# WEN-_2.net
KiCad netlist of a schematic drawn in EasyEDA Pro
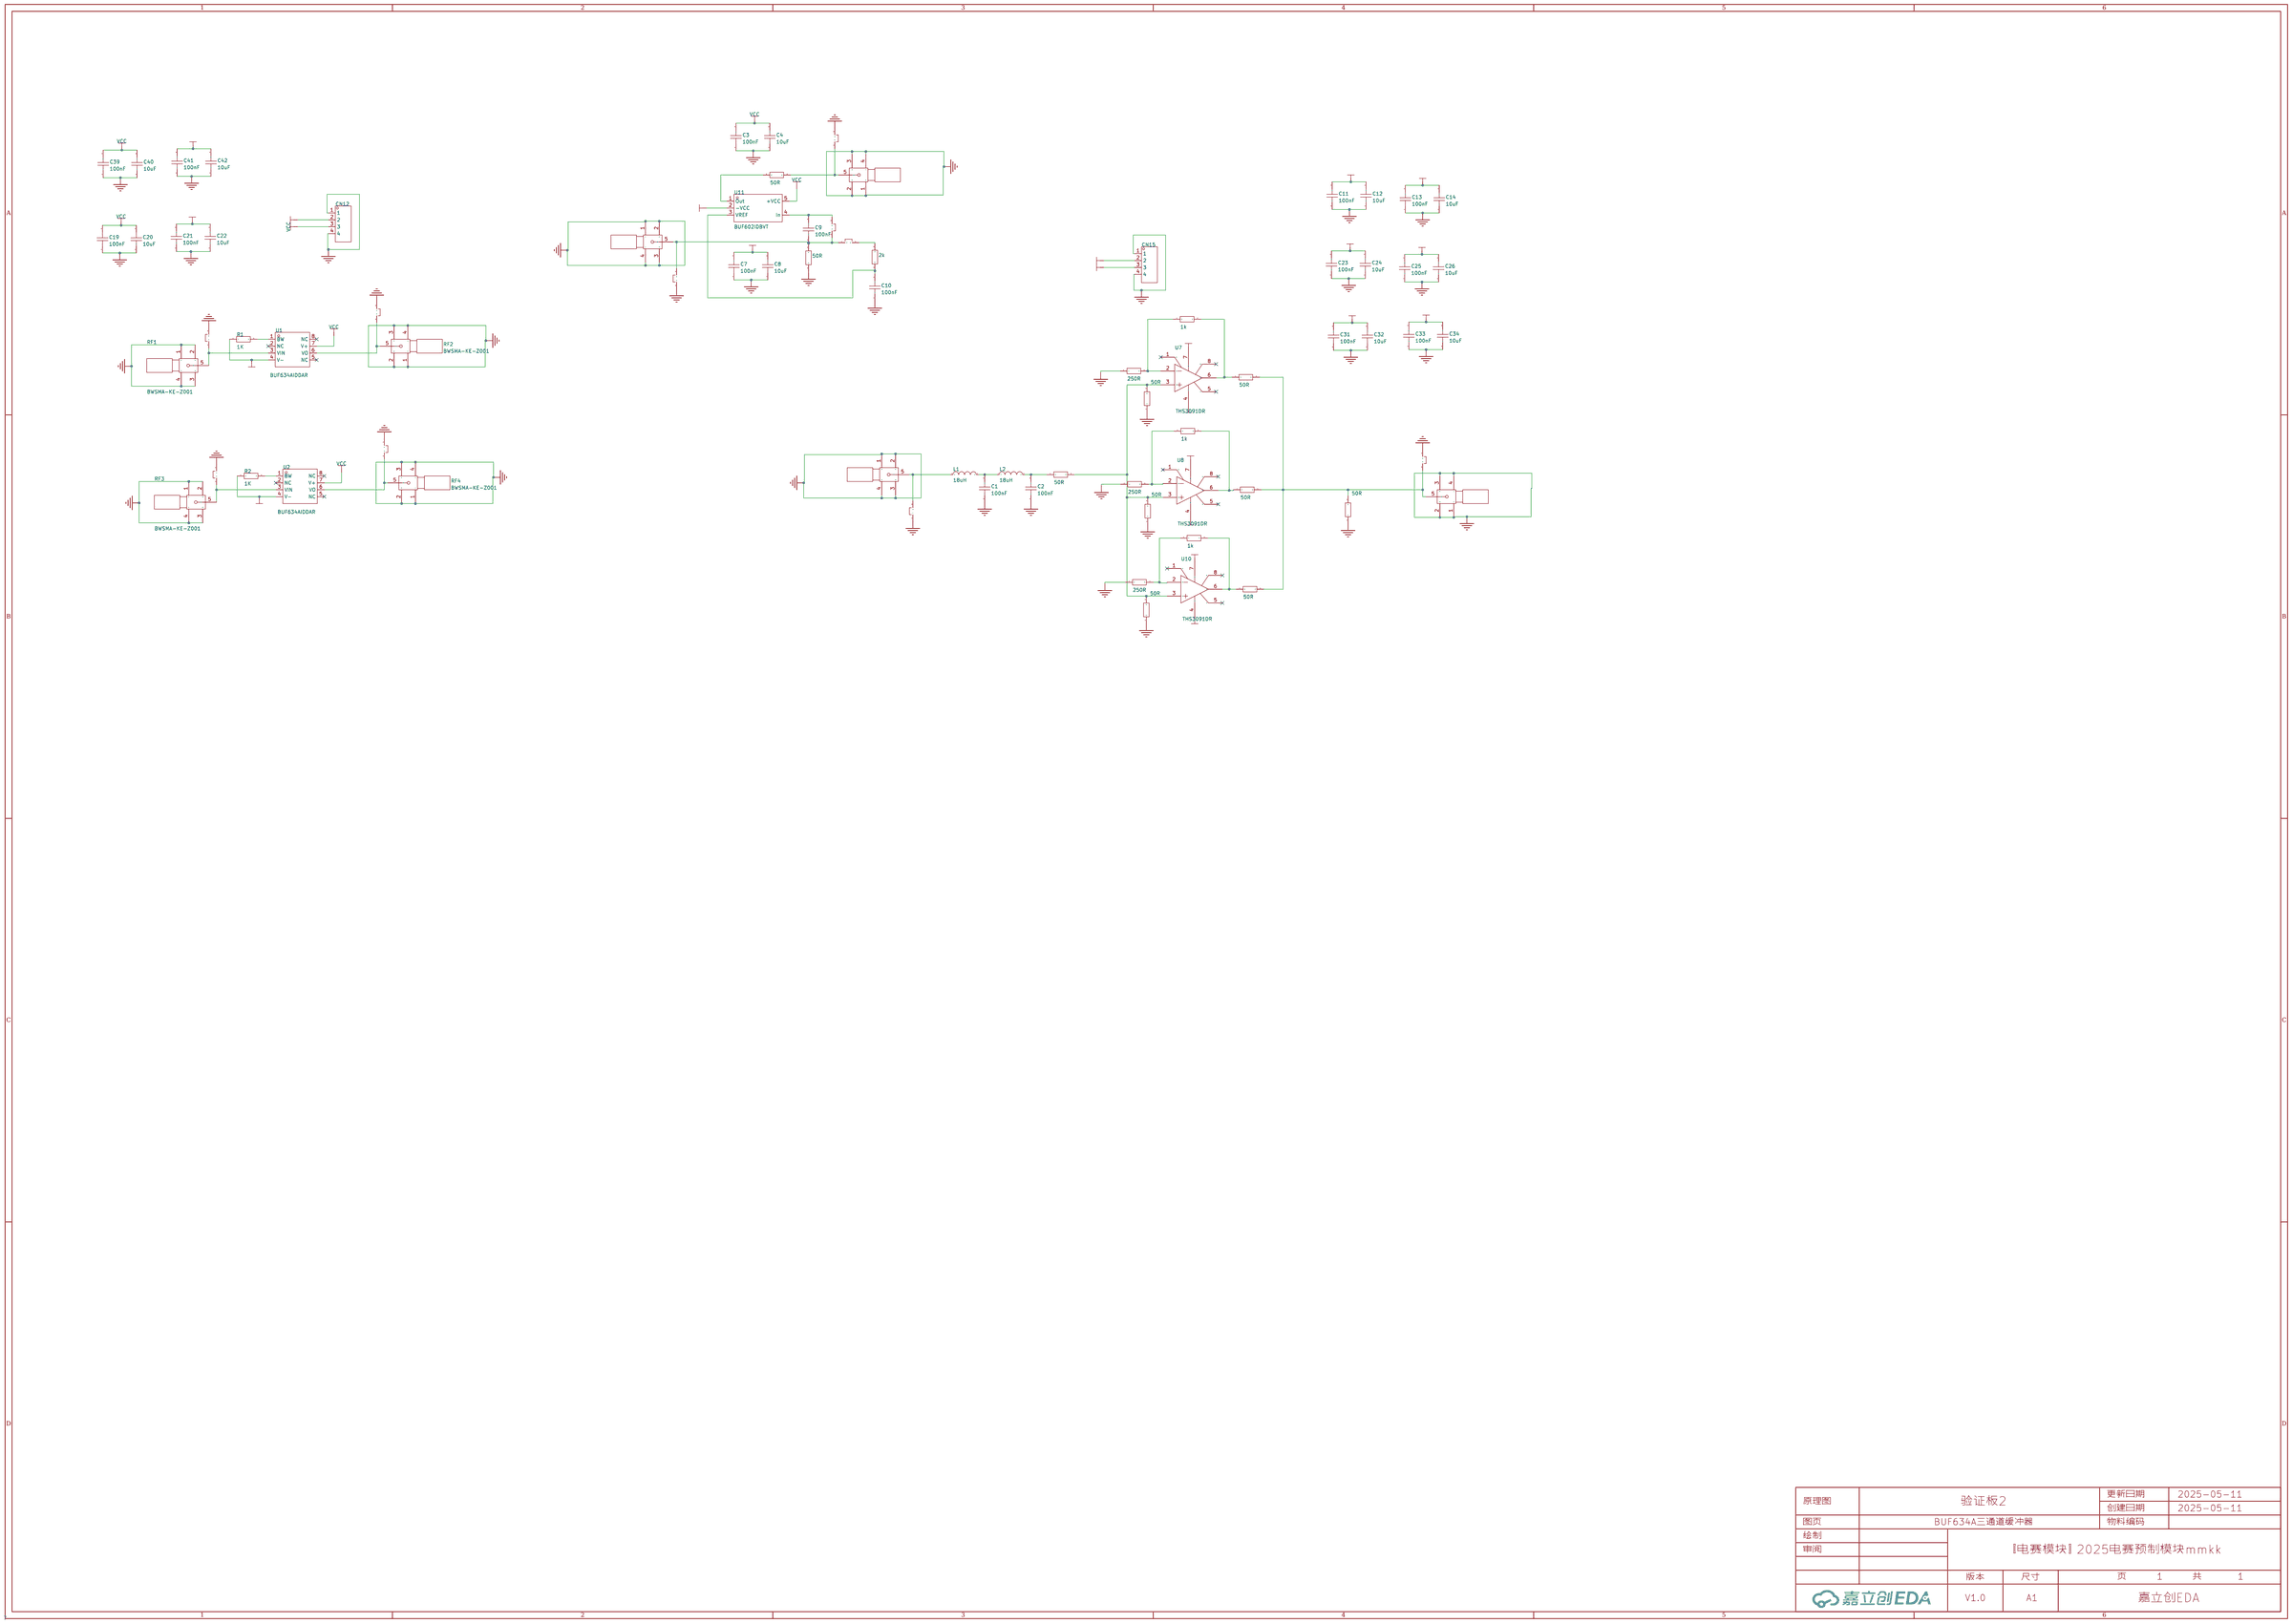
[diagram p0: schematic sheet]

(export (version "E")
  (design (tool "Eeschema 10.0.6"))
  (components
    (comp (ref "C1")
      (value "100nF")
      (footprint "easyedapro:C0805")
      (libsource (lib "easyedapro") (part "CapAcitance"))
    )
    (comp (ref "C2")
      (value "100nF")
      (footprint "easyedapro:C0805")
      (libsource (lib "easyedapro") (part "CapAcitance"))
    )
    (comp (ref "C3")
      (value "100nF")
      (footprint "easyedapro:C0805")
      (libsource (lib "easyedapro") (part "CapAcitance"))
    )
    (comp (ref "C4")
      (value "10uF")
      (footprint "easyedapro:C0805")
      (libsource (lib "easyedapro") (part "CapAcitance"))
    )
    (comp (ref "C7")
      (value "100nF")
      (footprint "easyedapro:C0805")
      (libsource (lib "easyedapro") (part "CapAcitance"))
    )
    (comp (ref "C8")
      (value "10uF")
      (footprint "easyedapro:C0805")
      (libsource (lib "easyedapro") (part "CapAcitance"))
    )
    (comp (ref "C9")
      (value "100nF")
      (footprint "easyedapro:C0805")
      (libsource (lib "easyedapro") (part "CapAcitance"))
    )
    (comp (ref "C10")
      (value "100nF")
      (footprint "easyedapro:C0805")
      (libsource (lib "easyedapro") (part "CapAcitance"))
    )
    (comp (ref "C11")
      (value "100nF")
      (footprint "easyedapro:C0805")
      (libsource (lib "easyedapro") (part "CapAcitance"))
    )
    (comp (ref "C12")
      (value "10uF")
      (footprint "easyedapro:C0805")
      (libsource (lib "easyedapro") (part "CapAcitance"))
    )
    (comp (ref "C13")
      (value "100nF")
      (footprint "easyedapro:C0805")
      (libsource (lib "easyedapro") (part "CapAcitance"))
    )
    (comp (ref "C14")
      (value "10uF")
      (footprint "easyedapro:C0805")
      (libsource (lib "easyedapro") (part "CapAcitance"))
    )
    (comp (ref "C19")
      (value "100nF")
      (footprint "easyedapro:C0805")
      (libsource (lib "easyedapro") (part "CapAcitance"))
    )
    (comp (ref "C20")
      (value "10uF")
      (footprint "easyedapro:C0805")
      (libsource (lib "easyedapro") (part "CapAcitance"))
    )
    (comp (ref "C21")
      (value "100nF")
      (footprint "easyedapro:C0805")
      (libsource (lib "easyedapro") (part "CapAcitance"))
    )
    (comp (ref "C22")
      (value "10uF")
      (footprint "easyedapro:C0805")
      (libsource (lib "easyedapro") (part "CapAcitance"))
    )
    (comp (ref "C23")
      (value "100nF")
      (footprint "easyedapro:C0805")
      (libsource (lib "easyedapro") (part "CapAcitance"))
    )
    (comp (ref "C24")
      (value "10uF")
      (footprint "easyedapro:C0805")
      (libsource (lib "easyedapro") (part "CapAcitance"))
    )
    (comp (ref "C25")
      (value "100nF")
      (footprint "easyedapro:C0805")
      (libsource (lib "easyedapro") (part "CapAcitance"))
    )
    (comp (ref "C26")
      (value "10uF")
      (footprint "easyedapro:C0805")
      (libsource (lib "easyedapro") (part "CapAcitance"))
    )
    (comp (ref "C31")
      (value "100nF")
      (footprint "easyedapro:C0805")
      (libsource (lib "easyedapro") (part "CapAcitance"))
    )
    (comp (ref "C32")
      (value "10uF")
      (footprint "easyedapro:C0805")
      (libsource (lib "easyedapro") (part "CapAcitance"))
    )
    (comp (ref "C33")
      (value "100nF")
      (footprint "easyedapro:C0805")
      (libsource (lib "easyedapro") (part "CapAcitance"))
    )
    (comp (ref "C34")
      (value "10uF")
      (footprint "easyedapro:C0805")
      (libsource (lib "easyedapro") (part "CapAcitance"))
    )
    (comp (ref "C39")
      (value "100nF")
      (footprint "easyedapro:C0805")
      (libsource (lib "easyedapro") (part "CapAcitance"))
    )
    (comp (ref "C40")
      (value "10uF")
      (footprint "easyedapro:C0805")
      (libsource (lib "easyedapro") (part "CapAcitance"))
    )
    (comp (ref "C41")
      (value "100nF")
      (footprint "easyedapro:C0805")
      (libsource (lib "easyedapro") (part "CapAcitance"))
    )
    (comp (ref "C42")
      (value "10uF")
      (footprint "easyedapro:C0805")
      (libsource (lib "easyedapro") (part "CapAcitance"))
    )
    (comp (ref "CN12")
      (value "WJ15EDGVC-3.81-4P")
      (footprint "easyedapro:CONN-TH_4P-P3.81_WJ2EDGVC-3.81-4P")
      (fields (field (name "Manufacturer") "KANGNEX(康奈克斯电气)"))
      (libsource (lib "easyedapro") (part "WJ15EDGVC-3.81-4P"))
    )
    (comp (ref "CN15")
      (value "WJ15EDGVC-3.81-4P")
      (footprint "easyedapro:CONN-TH_4P-P3.81_WJ2EDGVC-3.81-4P")
      (fields (field (name "Manufacturer") "KANGNEX(康奈克斯电气)"))
      (libsource (lib "easyedapro") (part "WJ15EDGVC-3.81-4P"))
    )
    (comp (ref "H1")
      (value "PZ254V-11-02P")
      (footprint "easyedapro:HDR-TH_2P-P2.54-V-M")
      (fields (field (name "Manufacturer") "XFCN(兴飞)"))
      (libsource (lib "easyedapro") (part "PZ254V-11-02P"))
    )
    (comp (ref "H2")
      (value "PZ254V-11-02P")
      (footprint "easyedapro:HDR-TH_2P-P2.54-V-M")
      (fields (field (name "Manufacturer") "XFCN(兴飞)"))
      (libsource (lib "easyedapro") (part "PZ254V-11-02P"))
    )
    (comp (ref "H3")
      (value "PZ254V-11-02P")
      (footprint "easyedapro:HDR-TH_2P-P2.54-V-M")
      (fields (field (name "Manufacturer") "XFCN(兴飞)"))
      (libsource (lib "easyedapro") (part "PZ254V-11-02P"))
    )
    (comp (ref "H4")
      (value "PZ254V-11-02P")
      (footprint "easyedapro:HDR-TH_2P-P2.54-V-M")
      (fields (field (name "Manufacturer") "XFCN(兴飞)"))
      (libsource (lib "easyedapro") (part "PZ254V-11-02P"))
    )
    (comp (ref "H5")
      (value "PZ254V-11-02P")
      (footprint "easyedapro:HDR-TH_2P-P2.54-V-M")
      (fields (field (name "Manufacturer") "XFCN(兴飞)"))
      (libsource (lib "easyedapro") (part "PZ254V-11-02P"))
    )
    (comp (ref "H6")
      (value "PZ254V-11-02P")
      (footprint "easyedapro:HDR-TH_2P-P2.54-V-M")
      (fields (field (name "Manufacturer") "XFCN(兴飞)"))
      (libsource (lib "easyedapro") (part "PZ254V-11-02P"))
    )
    (comp (ref "H7")
      (value "PZ254V-11-02P")
      (footprint "easyedapro:HDR-TH_2P-P2.54-V-M")
      (fields (field (name "Manufacturer") "XFCN(兴飞)"))
      (libsource (lib "easyedapro") (part "PZ254V-11-02P"))
    )
    (comp (ref "H8")
      (value "PZ254V-11-02P")
      (footprint "easyedapro:HDR-TH_2P-P2.54-V-M")
      (fields (field (name "Manufacturer") "XFCN(兴飞)"))
      (libsource (lib "easyedapro") (part "PZ254V-11-02P"))
    )
    (comp (ref "H9")
      (value "PZ254V-11-02P")
      (footprint "easyedapro:HDR-TH_2P-P2.54-V-M")
      (fields (field (name "Manufacturer") "XFCN(兴飞)"))
      (libsource (lib "easyedapro") (part "PZ254V-11-02P"))
    )
    (comp (ref "H10")
      (value "PZ254V-11-02P")
      (footprint "easyedapro:HDR-TH_2P-P2.54-V-M")
      (fields (field (name "Manufacturer") "XFCN(兴飞)"))
      (libsource (lib "easyedapro") (part "PZ254V-11-02P"))
    )
    (comp (ref "L1")
      (value "18uH")
      (footprint "easyedapro:L0805")
      (libsource (lib "easyedapro") (part "SDFL2012S100KTF"))
    )
    (comp (ref "L2")
      (value "18uH")
      (footprint "easyedapro:L0805")
      (libsource (lib "easyedapro") (part "SDFL2012S100KTF"))
    )
    (comp (ref "R1") (value "1K") (footprint "easyedapro:R0603") (libsource (lib "easyedapro") (part "电阻")))
    (comp (ref "R2") (value "1K") (footprint "easyedapro:R0603") (libsource (lib "easyedapro") (part "电阻")))
    (comp (ref "R7") (value "1K") (footprint "easyedapro:R0603") (libsource (lib "easyedapro") (part "电阻")))
    (comp (ref "R8") (value "1K") (footprint "easyedapro:R0603") (libsource (lib "easyedapro") (part "电阻")))
    (comp (ref "R10") (value "1K") (footprint "easyedapro:R0603") (libsource (lib "easyedapro") (part "电阻")))
    (comp (ref "R11") (value "1K") (footprint "easyedapro:R0603") (libsource (lib "easyedapro") (part "电阻")))
    (comp (ref "R12") (value "1K") (footprint "easyedapro:R0603") (libsource (lib "easyedapro") (part "电阻")))
    (comp (ref "R13") (value "1K") (footprint "easyedapro:R0603") (libsource (lib "easyedapro") (part "电阻")))
    (comp (ref "R14") (value "1K") (footprint "easyedapro:R0603") (libsource (lib "easyedapro") (part "电阻")))
    (comp (ref "R15") (value "1K") (footprint "easyedapro:R0603") (libsource (lib "easyedapro") (part "电阻")))
    (comp (ref "R16") (value "1K") (footprint "easyedapro:R0603") (libsource (lib "easyedapro") (part "电阻")))
    (comp (ref "R17") (value "1K") (footprint "easyedapro:R0603") (libsource (lib "easyedapro") (part "电阻")))
    (comp (ref "R18") (value "1K") (footprint "easyedapro:R0603") (libsource (lib "easyedapro") (part "电阻")))
    (comp (ref "R19") (value "1K") (footprint "easyedapro:R0603") (libsource (lib "easyedapro") (part "电阻")))
    (comp (ref "R22") (value "1K") (footprint "easyedapro:R0603") (libsource (lib "easyedapro") (part "电阻")))
    (comp (ref "R23") (value "1K") (footprint "easyedapro:R0603") (libsource (lib "easyedapro") (part "电阻")))
    (comp (ref "R24") (value "1K") (footprint "easyedapro:R0603") (libsource (lib "easyedapro") (part "电阻")))
    (comp (ref "R26") (value "1K") (footprint "easyedapro:R0603") (libsource (lib "easyedapro") (part "电阻")))
    (comp (ref "R27") (value "1K") (footprint "easyedapro:R0603") (libsource (lib "easyedapro") (part "电阻")))
    (comp (ref "RF1")
      (value "BWSMA-KE-Z001")
      (footprint "easyedapro:SMA-TH_BWSMA-KE-Z001")
      (fields (field (name "Manufacturer") "BAT WIRELESS(蝙蝠无线)"))
      (libsource (lib "easyedapro") (part "BWSMA-KE-Z001"))
    )
    (comp (ref "RF2")
      (value "BWSMA-KE-Z001")
      (footprint "easyedapro:SMA-TH_BWSMA-KE-Z001")
      (fields (field (name "Manufacturer") "BAT WIRELESS(蝙蝠无线)"))
      (libsource (lib "easyedapro") (part "BWSMA-KE-Z001"))
    )
    (comp (ref "RF3")
      (value "BWSMA-KE-Z001")
      (footprint "easyedapro:SMA-TH_BWSMA-KE-Z001")
      (fields (field (name "Manufacturer") "BAT WIRELESS(蝙蝠无线)"))
      (libsource (lib "easyedapro") (part "BWSMA-KE-Z001"))
    )
    (comp (ref "RF4")
      (value "BWSMA-KE-Z001")
      (footprint "easyedapro:SMA-TH_BWSMA-KE-Z001")
      (fields (field (name "Manufacturer") "BAT WIRELESS(蝙蝠无线)"))
      (libsource (lib "easyedapro") (part "BWSMA-KE-Z001"))
    )
    (comp (ref "RF5")
      (value "BWSMA-KE-Z001")
      (footprint "easyedapro:SMA-TH_BWSMA-KE-Z001")
      (fields (field (name "Manufacturer") "BAT WIRELESS(蝙蝠无线)"))
      (libsource (lib "easyedapro") (part "BWSMA-KE-Z001"))
    )
    (comp (ref "RF6")
      (value "BWSMA-KE-Z001")
      (footprint "easyedapro:SMA-TH_BWSMA-KE-Z001")
      (fields (field (name "Manufacturer") "BAT WIRELESS(蝙蝠无线)"))
      (libsource (lib "easyedapro") (part "BWSMA-KE-Z001"))
    )
    (comp (ref "RF7")
      (value "BWSMA-KE-Z001")
      (footprint "easyedapro:SMA-TH_BWSMA-KE-Z001")
      (fields (field (name "Manufacturer") "BAT WIRELESS(蝙蝠无线)"))
      (libsource (lib "easyedapro") (part "BWSMA-KE-Z001"))
    )
    (comp (ref "RF8")
      (value "BWSMA-KE-Z001")
      (footprint "easyedapro:SMA-TH_BWSMA-KE-Z001")
      (fields (field (name "Manufacturer") "BAT WIRELESS(蝙蝠无线)"))
      (libsource (lib "easyedapro") (part "BWSMA-KE-Z001"))
    )
    (comp (ref "U1")
      (value "BUF634AIDDAR")
      (footprint "easyedapro:SOIC-8_L4.9-W3.9-P1.27-LS6.0-BL")
      (description "放大器数:单路;轨到轨:-;增益带宽积(GBP):-;输入失调电压(Vos):65mV;压摆率(SR):3750V/us;输入偏置电流(Ib):250nA;")
      (fields (field (name "Manufacturer") "TI(德州仪器)"))
      (libsource (lib "easyedapro") (part "BUF634AIDDAR"))
    )
    (comp (ref "U2")
      (value "BUF634AIDDAR")
      (footprint "easyedapro:SOIC-8_L4.9-W3.9-P1.27-LS6.0-BL")
      (description "放大器数:单路;轨到轨:-;增益带宽积(GBP):-;输入失调电压(Vos):65mV;压摆率(SR):3750V/us;输入偏置电流(Ib):250nA;")
      (fields (field (name "Manufacturer") "TI(德州仪器)"))
      (libsource (lib "easyedapro") (part "BUF634AIDDAR"))
    )
    (comp (ref "U7")
      (value "THS3091DR")
      (footprint "easyedapro:SOIC-8_L4.9-W3.9-P1.27-LS6.0-BL")
      (description "放大器数:单路;增益带宽积(GBP):-;输入偏置电流(Ib):4uA;压摆率(SR):7300V/us;带宽(-3db):235MHz;")
      (fields (field (name "Manufacturer") "TI(德州仪器)"))
      (libsource (lib "easyedapro") (part "THS3091DR"))
    )
    (comp (ref "U8")
      (value "THS3091DR")
      (footprint "easyedapro:SOIC-8_L4.9-W3.9-P1.27-LS6.0-BL")
      (description "放大器数:单路;增益带宽积(GBP):-;输入偏置电流(Ib):4uA;压摆率(SR):7300V/us;带宽(-3db):235MHz;")
      (fields (field (name "Manufacturer") "TI(德州仪器)"))
      (libsource (lib "easyedapro") (part "THS3091DR"))
    )
    (comp (ref "U10")
      (value "THS3091DR")
      (footprint "easyedapro:SOIC-8_L4.9-W3.9-P1.27-LS6.0-BL")
      (description "放大器数:单路;增益带宽积(GBP):-;输入偏置电流(Ib):4uA;压摆率(SR):7300V/us;带宽(-3db):235MHz;")
      (fields (field (name "Manufacturer") "TI(德州仪器)"))
      (libsource (lib "easyedapro") (part "THS3091DR"))
    )
    (comp (ref "U11")
      (value "BUF602IDBVT")
      (footprint "easyedapro:SOT-23-5_L2.9-W1.6-P0.95-LS2.8-BL")
      (description "放大器数:单路;轨到轨:-;增益带宽积(GBP):1GHz;输入失调电压(Vos):30mV;压摆率(SR):8000V/us;输入偏置电流(Ib):3uA;")
      (fields (field (name "Manufacturer") "TI(德州仪器)"))
      (libsource (lib "easyedapro") (part "BUF602IDBVT"))
    )
  )
  (nets
    (net (code "1") (name "GND") (class "Default")
      (node (ref "C1") (pin "1") (pinfunction "1_1") (pintype "input"))
      (node (ref "C10") (pin "1") (pinfunction "1_1") (pintype "input"))
      (node (ref "C11") (pin "1") (pinfunction "1_1") (pintype "input"))
      (node (ref "C12") (pin "1") (pinfunction "1_1") (pintype "input"))
      (node (ref "C13") (pin "1") (pinfunction "1_1") (pintype "input"))
      (node (ref "C14") (pin "1") (pinfunction "1_1") (pintype "input"))
      (node (ref "C19") (pin "1") (pinfunction "1_1") (pintype "input"))
      (node (ref "C2") (pin "1") (pinfunction "1_1") (pintype "input"))
      (node (ref "C20") (pin "1") (pinfunction "1_1") (pintype "input"))
      (node (ref "C21") (pin "1") (pinfunction "1_1") (pintype "input"))
      (node (ref "C22") (pin "1") (pinfunction "1_1") (pintype "input"))
      (node (ref "C23") (pin "1") (pinfunction "1_1") (pintype "input"))
      (node (ref "C24") (pin "1") (pinfunction "1_1") (pintype "input"))
      (node (ref "C25") (pin "1") (pinfunction "1_1") (pintype "input"))
      (node (ref "C26") (pin "1") (pinfunction "1_1") (pintype "input"))
      (node (ref "C3") (pin "1") (pinfunction "1_1") (pintype "input"))
      (node (ref "C31") (pin "1") (pinfunction "1_1") (pintype "input"))
      (node (ref "C32") (pin "1") (pinfunction "1_1") (pintype "input"))
      (node (ref "C33") (pin "1") (pinfunction "1_1") (pintype "input"))
      (node (ref "C34") (pin "1") (pinfunction "1_1") (pintype "input"))
      (node (ref "C39") (pin "1") (pinfunction "1_1") (pintype "input"))
      (node (ref "C4") (pin "1") (pinfunction "1_1") (pintype "input"))
      (node (ref "C40") (pin "1") (pinfunction "1_1") (pintype "input"))
      (node (ref "C41") (pin "1") (pinfunction "1_1") (pintype "input"))
      (node (ref "C42") (pin "1") (pinfunction "1_1") (pintype "input"))
      (node (ref "C7") (pin "1") (pinfunction "1_1") (pintype "input"))
      (node (ref "C8") (pin "1") (pinfunction "1_1") (pintype "input"))
      (node (ref "CN12") (pin "1") (pinfunction "1_1") (pintype "unspecified"))
      (node (ref "CN12") (pin "4") (pinfunction "4_4") (pintype "unspecified"))
      (node (ref "CN15") (pin "1") (pinfunction "1_1") (pintype "unspecified"))
      (node (ref "CN15") (pin "4") (pinfunction "4_4") (pintype "unspecified"))
      (node (ref "H1") (pin "1") (pinfunction "1_1") (pintype "input"))
      (node (ref "H2") (pin "2") (pinfunction "2_2") (pintype "input"))
      (node (ref "H3") (pin "1") (pinfunction "1_1") (pintype "input"))
      (node (ref "H4") (pin "2") (pinfunction "2_2") (pintype "input"))
      (node (ref "H5") (pin "1") (pinfunction "1_1") (pintype "input"))
      (node (ref "H6") (pin "1") (pinfunction "1_1") (pintype "input"))
      (node (ref "H7") (pin "1") (pinfunction "1_1") (pintype "input"))
      (node (ref "H8") (pin "1") (pinfunction "1_1") (pintype "input"))
      (node (ref "R12") (pin "1") (pinfunction "1_1") (pintype "input"))
      (node (ref "R14") (pin "1") (pinfunction "1_1") (pintype "input"))
      (node (ref "R16") (pin "1") (pinfunction "1_1") (pintype "input"))
      (node (ref "R17") (pin "1") (pinfunction "1_1") (pintype "input"))
      (node (ref "R18") (pin "1") (pinfunction "1_1") (pintype "input"))
      (node (ref "R19") (pin "1") (pinfunction "1_1") (pintype "input"))
      (node (ref "R23") (pin "1") (pinfunction "1_1") (pintype "input"))
      (node (ref "R24") (pin "1") (pinfunction "1_1") (pintype "input"))
      (node (ref "RF1") (pin "1") (pinfunction "1_1") (pintype "unspecified"))
      (node (ref "RF1") (pin "2") (pinfunction "2_2") (pintype "unspecified"))
      (node (ref "RF1") (pin "3") (pinfunction "3_3") (pintype "unspecified"))
      (node (ref "RF1") (pin "4") (pinfunction "4_4") (pintype "unspecified"))
      (node (ref "RF2") (pin "1") (pinfunction "1_1") (pintype "unspecified"))
      (node (ref "RF2") (pin "2") (pinfunction "2_2") (pintype "unspecified"))
      (node (ref "RF2") (pin "3") (pinfunction "3_3") (pintype "unspecified"))
      (node (ref "RF2") (pin "4") (pinfunction "4_4") (pintype "unspecified"))
      (node (ref "RF3") (pin "1") (pinfunction "1_1") (pintype "unspecified"))
      (node (ref "RF3") (pin "2") (pinfunction "2_2") (pintype "unspecified"))
      (node (ref "RF3") (pin "3") (pinfunction "3_3") (pintype "unspecified"))
      (node (ref "RF3") (pin "4") (pinfunction "4_4") (pintype "unspecified"))
      (node (ref "RF4") (pin "1") (pinfunction "1_1") (pintype "unspecified"))
      (node (ref "RF4") (pin "2") (pinfunction "2_2") (pintype "unspecified"))
      (node (ref "RF4") (pin "3") (pinfunction "3_3") (pintype "unspecified"))
      (node (ref "RF4") (pin "4") (pinfunction "4_4") (pintype "unspecified"))
      (node (ref "RF5") (pin "1") (pinfunction "1_1") (pintype "unspecified"))
      (node (ref "RF5") (pin "2") (pinfunction "2_2") (pintype "unspecified"))
      (node (ref "RF5") (pin "3") (pinfunction "3_3") (pintype "unspecified"))
      (node (ref "RF5") (pin "4") (pinfunction "4_4") (pintype "unspecified"))
      (node (ref "RF6") (pin "1") (pinfunction "1_1") (pintype "unspecified"))
      (node (ref "RF6") (pin "2") (pinfunction "2_2") (pintype "unspecified"))
      (node (ref "RF6") (pin "3") (pinfunction "3_3") (pintype "unspecified"))
      (node (ref "RF6") (pin "4") (pinfunction "4_4") (pintype "unspecified"))
      (node (ref "RF7") (pin "1") (pinfunction "1_1") (pintype "unspecified"))
      (node (ref "RF7") (pin "2") (pinfunction "2_2") (pintype "unspecified"))
      (node (ref "RF7") (pin "3") (pinfunction "3_3") (pintype "unspecified"))
      (node (ref "RF7") (pin "4") (pinfunction "4_4") (pintype "unspecified"))
      (node (ref "RF8") (pin "1") (pinfunction "1_1") (pintype "unspecified"))
      (node (ref "RF8") (pin "2") (pinfunction "2_2") (pintype "unspecified"))
      (node (ref "RF8") (pin "3") (pinfunction "3_3") (pintype "unspecified"))
      (node (ref "RF8") (pin "4") (pinfunction "4_4") (pintype "unspecified"))
    )
    (net (code "2") (name "Net-(C1-Pad2)") (class "Default")
      (node (ref "C1") (pin "2") (pinfunction "2_2") (pintype "input"))
      (node (ref "L1") (pin "2") (pinfunction "2_2") (pintype "unspecified"))
      (node (ref "L2") (pin "1") (pinfunction "1_1") (pintype "unspecified"))
    )
    (net (code "3") (name "Net-(C2-Pad2)") (class "Default")
      (node (ref "C2") (pin "2") (pinfunction "2_2") (pintype "input"))
      (node (ref "L2") (pin "2") (pinfunction "2_2") (pintype "unspecified"))
      (node (ref "R22") (pin "1") (pinfunction "1_1") (pintype "input"))
    )
    (net (code "4") (name "Net-(C9-Pad1)") (class "Default")
      (node (ref "C9") (pin "1") (pinfunction "1_1") (pintype "input"))
      (node (ref "H10") (pin "1") (pinfunction "1_1") (pintype "input"))
      (node (ref "H7") (pin "2") (pinfunction "2_2") (pintype "input"))
      (node (ref "H9") (pin "2") (pinfunction "2_2") (pintype "input"))
      (node (ref "R24") (pin "2") (pinfunction "2_2") (pintype "input"))
      (node (ref "RF7") (pin "5") (pinfunction "5_5") (pintype "unspecified"))
    )
    (net (code "5") (name "Net-(H5-Pad2)") (class "Default")
      (node (ref "H5") (pin "2") (pinfunction "2_2") (pintype "input"))
      (node (ref "L1") (pin "1") (pinfunction "1_1") (pintype "unspecified"))
      (node (ref "RF5") (pin "5") (pinfunction "5_5") (pintype "unspecified"))
    )
    (net (code "6") (name "Net-(H6-Pad2)") (class "Default")
      (node (ref "H6") (pin "2") (pinfunction "2_2") (pintype "input"))
      (node (ref "R10") (pin "2") (pinfunction "2_2") (pintype "input"))
      (node (ref "R23") (pin "2") (pinfunction "2_2") (pintype "input"))
      (node (ref "R7") (pin "2") (pinfunction "2_2") (pintype "input"))
      (node (ref "R8") (pin "2") (pinfunction "2_2") (pintype "input"))
      (node (ref "RF6") (pin "5") (pinfunction "5_5") (pintype "unspecified"))
    )
    (net (code "7") (name "Net-(H8-Pad2)") (class "Default")
      (node (ref "H8") (pin "2") (pinfunction "2_2") (pintype "input"))
      (node (ref "R26") (pin "1") (pinfunction "1_1") (pintype "input"))
      (node (ref "RF8") (pin "5") (pinfunction "5_5") (pintype "unspecified"))
    )
    (net (code "8") (name "Net-(H10-Pad2)") (class "Default")
      (node (ref "H10") (pin "2") (pinfunction "2_2") (pintype "input"))
      (node (ref "R27") (pin "2") (pinfunction "2_2") (pintype "input"))
    )
    (net (code "9") (name "Net-(U1-BW)") (class "Default")
      (node (ref "R1") (pin "2") (pinfunction "2_2") (pintype "input"))
      (node (ref "U1") (pin "1") (pinfunction "BW_1") (pintype "unspecified"))
    )
    (net (code "10") (name "Net-(U1-VIN)") (class "Default")
      (node (ref "H2") (pin "1") (pinfunction "1_1") (pintype "input"))
      (node (ref "RF1") (pin "5") (pinfunction "5_5") (pintype "unspecified"))
      (node (ref "U1") (pin "3") (pinfunction "VIN_3") (pintype "unspecified"))
    )
    (net (code "11") (name "Net-(U1-VO)") (class "Default")
      (node (ref "H1") (pin "2") (pinfunction "2_2") (pintype "input"))
      (node (ref "RF2") (pin "5") (pinfunction "5_5") (pintype "unspecified"))
      (node (ref "U1") (pin "6") (pinfunction "VO_6") (pintype "unspecified"))
    )
    (net (code "12") (name "Net-(U2-BW)") (class "Default")
      (node (ref "R2") (pin "2") (pinfunction "2_2") (pintype "input"))
      (node (ref "U2") (pin "1") (pinfunction "BW_1") (pintype "unspecified"))
    )
    (net (code "13") (name "Net-(U2-VIN)") (class "Default")
      (node (ref "H4") (pin "1") (pinfunction "1_1") (pintype "input"))
      (node (ref "RF3") (pin "5") (pinfunction "5_5") (pintype "unspecified"))
      (node (ref "U2") (pin "3") (pinfunction "VIN_3") (pintype "unspecified"))
    )
    (net (code "14") (name "Net-(U2-VO)") (class "Default")
      (node (ref "H3") (pin "2") (pinfunction "2_2") (pintype "input"))
      (node (ref "RF4") (pin "5") (pinfunction "5_5") (pintype "unspecified"))
      (node (ref "U2") (pin "6") (pinfunction "VO_6") (pintype "unspecified"))
    )
    (net (code "15") (name "Net-(U7-VIN-)") (class "Default")
      (node (ref "R11") (pin "1") (pinfunction "1_1") (pintype "input"))
      (node (ref "R12") (pin "2") (pinfunction "2_2") (pintype "input"))
      (node (ref "U7") (pin "2") (pinfunction "VIN-_2") (pintype "unspecified"))
    )
    (net (code "16") (name "Net-(U7-VOUT)") (class "Default")
      (node (ref "R11") (pin "2") (pinfunction "2_2") (pintype "input"))
      (node (ref "R7") (pin "1") (pinfunction "1_1") (pintype "input"))
      (node (ref "U7") (pin "6") (pinfunction "VOUT_6") (pintype "output"))
    )
    (net (code "17") (name "Net-(U8-VIN-)") (class "Default")
      (node (ref "R13") (pin "1") (pinfunction "1_1") (pintype "input"))
      (node (ref "R14") (pin "2") (pinfunction "2_2") (pintype "input"))
      (node (ref "U8") (pin "2") (pinfunction "VIN-_2") (pintype "unspecified"))
    )
    (net (code "18") (name "Net-(U8-VOUT)") (class "Default")
      (node (ref "R13") (pin "2") (pinfunction "2_2") (pintype "input"))
      (node (ref "R8") (pin "1") (pinfunction "1_1") (pintype "input"))
      (node (ref "U8") (pin "6") (pinfunction "VOUT_6") (pintype "output"))
    )
    (net (code "19") (name "Net-(U10-VIN+)") (class "Default")
      (node (ref "R17") (pin "2") (pinfunction "2_2") (pintype "input"))
      (node (ref "R18") (pin "2") (pinfunction "2_2") (pintype "input"))
      (node (ref "R19") (pin "2") (pinfunction "2_2") (pintype "input"))
      (node (ref "R22") (pin "2") (pinfunction "2_2") (pintype "input"))
      (node (ref "U10") (pin "3") (pinfunction "VIN+_3") (pintype "unspecified"))
      (node (ref "U7") (pin "3") (pinfunction "VIN+_3") (pintype "unspecified"))
      (node (ref "U8") (pin "3") (pinfunction "VIN+_3") (pintype "unspecified"))
    )
    (net (code "20") (name "Net-(U10-VIN-)") (class "Default")
      (node (ref "R15") (pin "1") (pinfunction "1_1") (pintype "input"))
      (node (ref "R16") (pin "2") (pinfunction "2_2") (pintype "input"))
      (node (ref "U10") (pin "2") (pinfunction "VIN-_2") (pintype "unspecified"))
    )
    (net (code "21") (name "Net-(U10-VOUT)") (class "Default")
      (node (ref "R10") (pin "1") (pinfunction "1_1") (pintype "input"))
      (node (ref "R15") (pin "2") (pinfunction "2_2") (pintype "input"))
      (node (ref "U10") (pin "6") (pinfunction "VOUT_6") (pintype "output"))
    )
    (net (code "22") (name "Net-(U11-In)") (class "Default")
      (node (ref "C9") (pin "2") (pinfunction "2_2") (pintype "input"))
      (node (ref "H9") (pin "1") (pinfunction "1_1") (pintype "input"))
      (node (ref "U11") (pin "4") (pinfunction "In_4") (pintype "unspecified"))
    )
    (net (code "23") (name "Net-(U11-Out)") (class "Default")
      (node (ref "R26") (pin "2") (pinfunction "2_2") (pintype "input"))
      (node (ref "U11") (pin "1") (pinfunction "Out_1") (pintype "unspecified"))
    )
    (net (code "24") (name "Net-(U11-VREF)") (class "Default")
      (node (ref "C10") (pin "2") (pinfunction "2_2") (pintype "input"))
      (node (ref "R27") (pin "1") (pinfunction "1_1") (pintype "input"))
      (node (ref "U11") (pin "3") (pinfunction "VREF_3") (pintype "unspecified"))
    )
    (net (code "25") (name "VCC") (class "Default")
      (node (ref "C19") (pin "2") (pinfunction "2_2") (pintype "input"))
      (node (ref "C20") (pin "2") (pinfunction "2_2") (pintype "input"))
      (node (ref "C3") (pin "2") (pinfunction "2_2") (pintype "input"))
      (node (ref "C39") (pin "2") (pinfunction "2_2") (pintype "input"))
      (node (ref "C4") (pin "2") (pinfunction "2_2") (pintype "input"))
      (node (ref "C40") (pin "2") (pinfunction "2_2") (pintype "input"))
      (node (ref "CN12") (pin "3") (pinfunction "3_3") (pintype "unspecified"))
      (node (ref "U1") (pin "7") (pinfunction "V+_7") (pintype "unspecified"))
      (node (ref "U11") (pin "5") (pinfunction "+VCC_5") (pintype "unspecified"))
      (node (ref "U2") (pin "7") (pinfunction "V+_7") (pintype "unspecified"))
    )
    (net (code "26") (name "VDD") (class "Default")
      (node (ref "C11") (pin "2") (pinfunction "2_2") (pintype "input"))
      (node (ref "C12") (pin "2") (pinfunction "2_2") (pintype "input"))
      (node (ref "C23") (pin "2") (pinfunction "2_2") (pintype "input"))
      (node (ref "C24") (pin "2") (pinfunction "2_2") (pintype "input"))
      (node (ref "C31") (pin "2") (pinfunction "2_2") (pintype "input"))
      (node (ref "C32") (pin "2") (pinfunction "2_2") (pintype "input"))
      (node (ref "CN15") (pin "2") (pinfunction "2_2") (pintype "unspecified"))
      (node (ref "U10") (pin "7") (pinfunction "VS+_7") (pintype "unspecified"))
      (node (ref "U7") (pin "7") (pinfunction "VS+_7") (pintype "unspecified"))
      (node (ref "U8") (pin "7") (pinfunction "VS+_7") (pintype "unspecified"))
    )
    (net (code "27") (name "VEE") (class "Default")
      (node (ref "C21") (pin "2") (pinfunction "2_2") (pintype "input"))
      (node (ref "C22") (pin "2") (pinfunction "2_2") (pintype "input"))
      (node (ref "C41") (pin "2") (pinfunction "2_2") (pintype "input"))
      (node (ref "C42") (pin "2") (pinfunction "2_2") (pintype "input"))
      (node (ref "C7") (pin "2") (pinfunction "2_2") (pintype "input"))
      (node (ref "C8") (pin "2") (pinfunction "2_2") (pintype "input"))
      (node (ref "CN12") (pin "2") (pinfunction "2_2") (pintype "unspecified"))
      (node (ref "R1") (pin "1") (pinfunction "1_1") (pintype "input"))
      (node (ref "R2") (pin "1") (pinfunction "1_1") (pintype "input"))
      (node (ref "U1") (pin "4") (pinfunction "V-_4") (pintype "unspecified"))
      (node (ref "U11") (pin "2") (pinfunction "−VCC_2") (pintype "unspecified"))
      (node (ref "U2") (pin "4") (pinfunction "V-_4") (pintype "unspecified"))
    )
    (net (code "28") (name "VSS") (class "Default")
      (node (ref "C13") (pin "2") (pinfunction "2_2") (pintype "input"))
      (node (ref "C14") (pin "2") (pinfunction "2_2") (pintype "input"))
      (node (ref "C25") (pin "2") (pinfunction "2_2") (pintype "input"))
      (node (ref "C26") (pin "2") (pinfunction "2_2") (pintype "input"))
      (node (ref "C33") (pin "2") (pinfunction "2_2") (pintype "input"))
      (node (ref "C34") (pin "2") (pinfunction "2_2") (pintype "input"))
      (node (ref "CN15") (pin "3") (pinfunction "3_3") (pintype "unspecified"))
      (node (ref "U10") (pin "4") (pinfunction "VS-_4") (pintype "unspecified"))
      (node (ref "U7") (pin "4") (pinfunction "VS-_4") (pintype "unspecified"))
      (node (ref "U8") (pin "4") (pinfunction "VS-_4") (pintype "unspecified"))
    )
    (net (code "29") (name "unconnected-(U1-NC-Pad2)") (class "Default")
      (node (ref "U1") (pin "2") (pinfunction "NC_2") (pintype "unspecified+no_connect"))
    )
    (net (code "30") (name "unconnected-(U1-NC-Pad5)") (class "Default")
      (node (ref "U1") (pin "5") (pinfunction "NC_5") (pintype "unspecified+no_connect"))
    )
    (net (code "31") (name "unconnected-(U1-NC-Pad8)") (class "Default")
      (node (ref "U1") (pin "8") (pinfunction "NC_8") (pintype "unspecified+no_connect"))
    )
    (net (code "32") (name "unconnected-(U2-NC-Pad2)") (class "Default")
      (node (ref "U2") (pin "2") (pinfunction "NC_2") (pintype "unspecified+no_connect"))
    )
    (net (code "33") (name "unconnected-(U2-NC-Pad5)") (class "Default")
      (node (ref "U2") (pin "5") (pinfunction "NC_5") (pintype "unspecified+no_connect"))
    )
    (net (code "34") (name "unconnected-(U2-NC-Pad8)") (class "Default")
      (node (ref "U2") (pin "8") (pinfunction "NC_8") (pintype "unspecified+no_connect"))
    )
    (net (code "35") (name "unconnected-(U7-NC-Pad1)") (class "Default")
      (node (ref "U7") (pin "1") (pinfunction "NC_1") (pintype "unspecified+no_connect"))
    )
    (net (code "36") (name "unconnected-(U7-NC-Pad5)") (class "Default")
      (node (ref "U7") (pin "5") (pinfunction "NC_5") (pintype "unspecified+no_connect"))
    )
    (net (code "37") (name "unconnected-(U7-NC-Pad8)") (class "Default")
      (node (ref "U7") (pin "8") (pinfunction "NC_8") (pintype "unspecified+no_connect"))
    )
    (net (code "38") (name "unconnected-(U8-NC-Pad1)") (class "Default")
      (node (ref "U8") (pin "1") (pinfunction "NC_1") (pintype "unspecified+no_connect"))
    )
    (net (code "39") (name "unconnected-(U8-NC-Pad5)") (class "Default")
      (node (ref "U8") (pin "5") (pinfunction "NC_5") (pintype "unspecified+no_connect"))
    )
    (net (code "40") (name "unconnected-(U8-NC-Pad8)") (class "Default")
      (node (ref "U8") (pin "8") (pinfunction "NC_8") (pintype "unspecified+no_connect"))
    )
    (net (code "41") (name "unconnected-(U10-NC-Pad1)") (class "Default")
      (node (ref "U10") (pin "1") (pinfunction "NC_1") (pintype "unspecified+no_connect"))
    )
    (net (code "42") (name "unconnected-(U10-NC-Pad5)") (class "Default")
      (node (ref "U10") (pin "5") (pinfunction "NC_5") (pintype "unspecified+no_connect"))
    )
    (net (code "43") (name "unconnected-(U10-NC-Pad8)") (class "Default")
      (node (ref "U10") (pin "8") (pinfunction "NC_8") (pintype "unspecified+no_connect"))
    )
  )
)
